# can-universalmodul.net
KiCad netlist of a schematic drawn in EAGLE
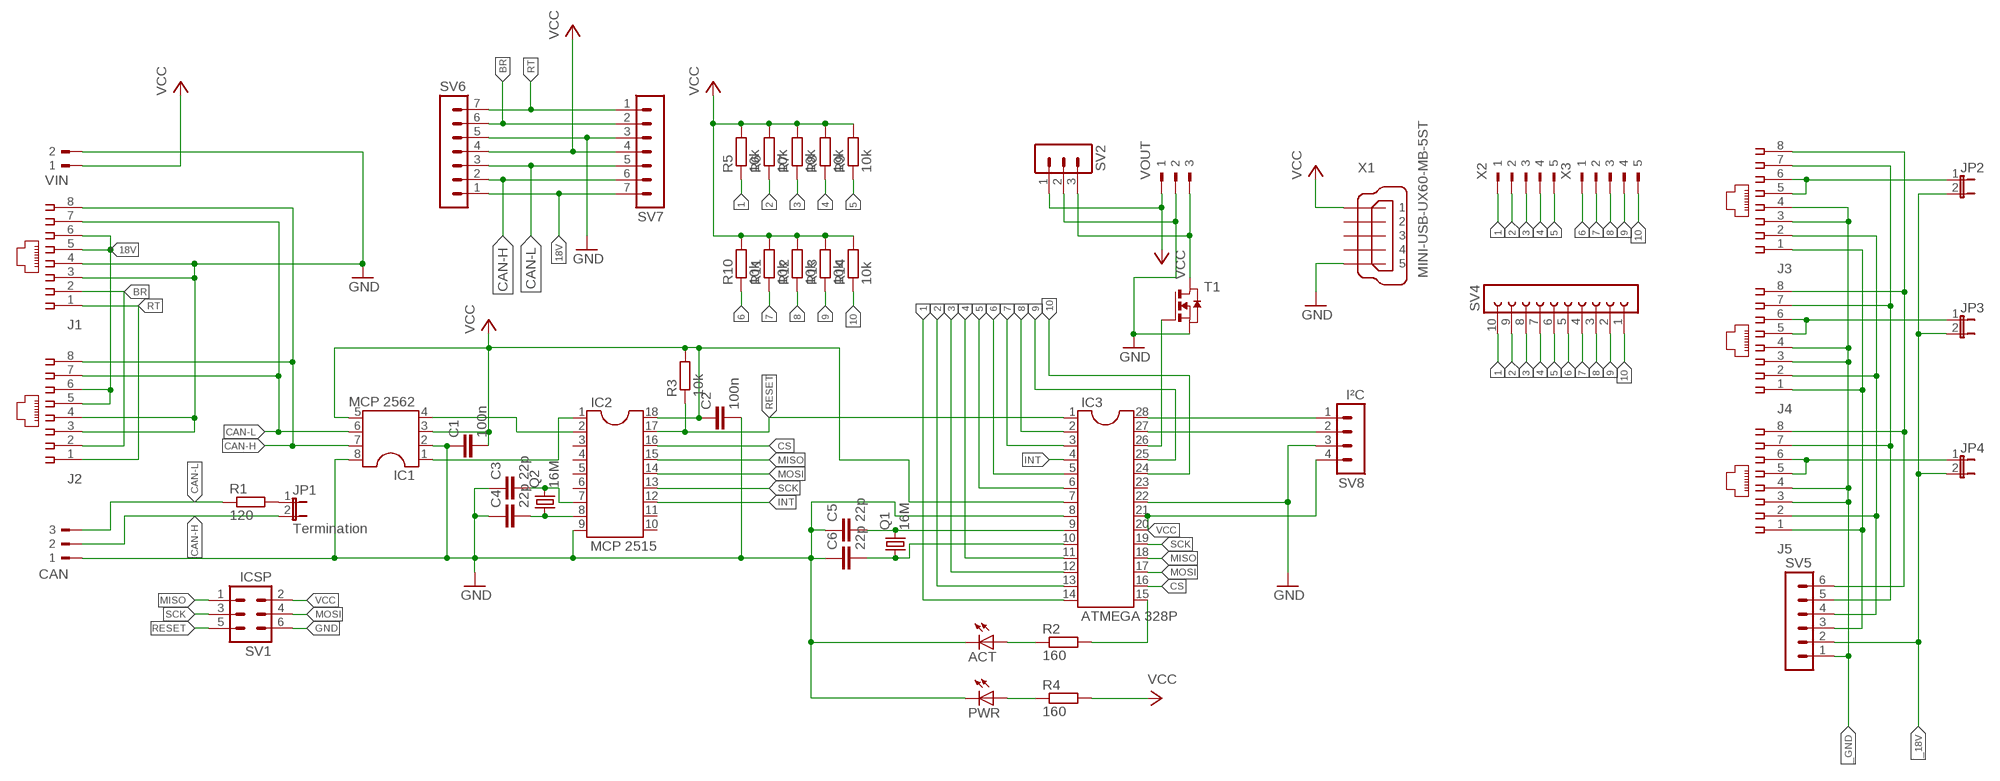
[diagram p0: schematic, sheet 1]

(export (version "E")
  (design (tool "Eeschema 10.0.6"))
  (components
    (comp (ref "ACT")
      (value "LEDCHIP-LED0805")
      (footprint "eagle-import:CHIP-LED0805")
      (libsource (lib "eagle-import") (part "LEDCHIP-LED0805"))
    )
    (comp (ref "C1")
      (value "100n")
      (footprint "eagle-import:C0805K")
      (libsource (lib "eagle-import") (part "C-EUC0805K"))
    )
    (comp (ref "C2")
      (value "100n")
      (footprint "eagle-import:C0805K")
      (libsource (lib "eagle-import") (part "C-EUC0805K"))
    )
    (comp (ref "C3")
      (value "22p")
      (footprint "eagle-import:C0805K")
      (libsource (lib "eagle-import") (part "C-EUC0805K"))
    )
    (comp (ref "C4")
      (value "22p")
      (footprint "eagle-import:C0805K")
      (libsource (lib "eagle-import") (part "C-EUC0805K"))
    )
    (comp (ref "C5")
      (value "22p")
      (footprint "eagle-import:C0805K")
      (libsource (lib "eagle-import") (part "C-EUC0805K"))
    )
    (comp (ref "C6")
      (value "22p")
      (footprint "eagle-import:C0805K")
      (libsource (lib "eagle-import") (part "C-EUC0805K"))
    )
    (comp (ref "CAN")
      (value "90-3")
      (footprint "eagle-import:90-3")
      (libsource (lib "eagle-import") (part "90-3"))
    )
    (comp (ref "IC1")
      (value "MCP 2562")
      (footprint "eagle-import:SOCKET-08")
      (libsource (lib "eagle-import") (part "DIL8S"))
    )
    (comp (ref "IC2")
      (value "MCP 2515")
      (footprint "eagle-import:SOCKET-18")
      (libsource (lib "eagle-import") (part "DIL18S"))
    )
    (comp (ref "IC3")
      (value "ATMEGA 328P")
      (footprint "eagle-import:DIL28-3")
      (libsource (lib "eagle-import") (part "DIL28-3"))
    )
    (comp (ref "J1")
      (value "215877-7")
      (footprint "eagle-import:215877-7")
      (libsource (lib "eagle-import") (part "215877-7"))
    )
    (comp (ref "J2")
      (value "215877-7")
      (footprint "eagle-import:215877-7")
      (libsource (lib "eagle-import") (part "215877-7"))
    )
    (comp (ref "J3")
      (value "215877-7")
      (footprint "eagle-import:215877-7")
      (libsource (lib "eagle-import") (part "215877-7"))
    )
    (comp (ref "J4")
      (value "215877-7")
      (footprint "eagle-import:215877-7")
      (libsource (lib "eagle-import") (part "215877-7"))
    )
    (comp (ref "J5")
      (value "215877-7")
      (footprint "eagle-import:215877-7")
      (libsource (lib "eagle-import") (part "215877-7"))
    )
    (comp (ref "JP1")
      (value "Termination")
      (footprint "eagle-import:JP1")
      (libsource (lib "eagle-import") (part "JP1E"))
    )
    (comp (ref "JP2")
      (value "JP1E")
      (footprint "eagle-import:JP1")
      (libsource (lib "eagle-import") (part "JP1E"))
    )
    (comp (ref "JP3")
      (value "JP1E")
      (footprint "eagle-import:JP1")
      (libsource (lib "eagle-import") (part "JP1E"))
    )
    (comp (ref "JP4")
      (value "JP1E")
      (footprint "eagle-import:JP1")
      (libsource (lib "eagle-import") (part "JP1E"))
    )
    (comp (ref "PWR")
      (value "LEDCHIP-LED0805")
      (footprint "eagle-import:CHIP-LED0805")
      (libsource (lib "eagle-import") (part "LEDCHIP-LED0805"))
    )
    (comp (ref "Q1")
      (value "16M")
      (footprint "eagle-import:CSM-7X-DU")
      (libsource (lib "eagle-import") (part "CSM-7X-DU"))
    )
    (comp (ref "Q2")
      (value "16M")
      (footprint "eagle-import:CSM-7X-DU")
      (libsource (lib "eagle-import") (part "CSM-7X-DU"))
    )
    (comp (ref "R1")
      (value "120")
      (footprint "eagle-import:R0805")
      (libsource (lib "eagle-import") (part "R-EU_R0805"))
    )
    (comp (ref "R2")
      (value "160")
      (footprint "eagle-import:R0805")
      (libsource (lib "eagle-import") (part "R-EU_R0805"))
    )
    (comp (ref "R3")
      (value "10k")
      (footprint "eagle-import:R0805")
      (libsource (lib "eagle-import") (part "R-EU_R0805"))
    )
    (comp (ref "R4")
      (value "160")
      (footprint "eagle-import:R0805")
      (libsource (lib "eagle-import") (part "R-EU_R0805"))
    )
    (comp (ref "R5")
      (value "10k")
      (footprint "eagle-import:R0805")
      (libsource (lib "eagle-import") (part "R-EU_R0805"))
    )
    (comp (ref "R6")
      (value "10k")
      (footprint "eagle-import:R0805")
      (libsource (lib "eagle-import") (part "R-EU_R0805"))
    )
    (comp (ref "R7")
      (value "10k")
      (footprint "eagle-import:R0805")
      (libsource (lib "eagle-import") (part "R-EU_R0805"))
    )
    (comp (ref "R8")
      (value "10k")
      (footprint "eagle-import:R0805")
      (libsource (lib "eagle-import") (part "R-EU_R0805"))
    )
    (comp (ref "R9")
      (value "10k")
      (footprint "eagle-import:R0805")
      (libsource (lib "eagle-import") (part "R-EU_R0805"))
    )
    (comp (ref "R10")
      (value "10k")
      (footprint "eagle-import:R0805")
      (libsource (lib "eagle-import") (part "R-EU_R0805"))
    )
    (comp (ref "R11")
      (value "10k")
      (footprint "eagle-import:R0805")
      (libsource (lib "eagle-import") (part "R-EU_R0805"))
    )
    (comp (ref "R12")
      (value "10k")
      (footprint "eagle-import:R0805")
      (libsource (lib "eagle-import") (part "R-EU_R0805"))
    )
    (comp (ref "R13")
      (value "10k")
      (footprint "eagle-import:R0805")
      (libsource (lib "eagle-import") (part "R-EU_R0805"))
    )
    (comp (ref "R14")
      (value "10k")
      (footprint "eagle-import:R0805")
      (libsource (lib "eagle-import") (part "R-EU_R0805"))
    )
    (comp (ref "SV1")
      (value "ICSP")
      (footprint "eagle-import:MA03-2")
      (libsource (lib "eagle-import") (part "MA03-2"))
    )
    (comp (ref "SV2")
      (value "MA03-1")
      (footprint "eagle-import:MA03-1")
      (libsource (lib "eagle-import") (part "MA03-1"))
    )
    (comp (ref "SV4")
      (value "FE10W")
      (footprint "eagle-import:FE10W")
      (libsource (lib "eagle-import") (part "FE10W"))
    )
    (comp (ref "SV5")
      (value "MA06-1")
      (footprint "eagle-import:MA06-1")
      (libsource (lib "eagle-import") (part "MA06-1"))
    )
    (comp (ref "SV6")
      (value "MA07-1")
      (footprint "eagle-import:MA07-1")
      (libsource (lib "eagle-import") (part "MA07-1"))
    )
    (comp (ref "SV7")
      (value "MA07-1")
      (footprint "eagle-import:MA07-1")
      (libsource (lib "eagle-import") (part "MA07-1"))
    )
    (comp (ref "SV8")
      (value "I²C")
      (footprint "eagle-import:MA04-1")
      (libsource (lib "eagle-import") (part "MA04-1"))
    )
    (comp (ref "T1")
      (value "NMOSSOT23")
      (footprint "eagle-import:SOT-23")
      (libsource (lib "eagle-import") (part "NMOSSOT23"))
    )
    (comp (ref "VIN")
      (value "90-2")
      (footprint "eagle-import:90-2")
      (libsource (lib "eagle-import") (part "90-2"))
    )
    (comp (ref "VOUT")
      (value "90-3")
      (footprint "eagle-import:90-3")
      (libsource (lib "eagle-import") (part "90-3"))
    )
    (comp (ref "X1")
      (value "MINI-USB-UX60-MB-5ST")
      (footprint "eagle-import:UX60-MB-5ST")
      (libsource (lib "eagle-import") (part "MINI-USB-UX60-MB-5ST"))
    )
    (comp (ref "X2")
      (value "90-5")
      (footprint "eagle-import:90-5")
      (libsource (lib "eagle-import") (part "90-5"))
    )
    (comp (ref "X3")
      (value "90-5")
      (footprint "eagle-import:90-5")
      (libsource (lib "eagle-import") (part "90-5"))
    )
  )
  (nets
    (net (code "1") (name "1") (class "Default")
      (node (ref "IC3") (pin "14") (pinfunction "14_14") (pintype "passive"))
      (node (ref "R5") (pin "1") (pinfunction "1_1") (pintype "passive"))
      (node (ref "SV4") (pin "10") (pinfunction "10_10") (pintype "passive"))
      (node (ref "X2") (pin "1") (pinfunction "1_1") (pintype "passive"))
    )
    (net (code "2") (name "2") (class "Default")
      (node (ref "IC3") (pin "13") (pinfunction "13_13") (pintype "passive"))
      (node (ref "R6") (pin "1") (pinfunction "1_1") (pintype "passive"))
      (node (ref "SV4") (pin "9") (pinfunction "9_9") (pintype "passive"))
      (node (ref "X2") (pin "2") (pinfunction "2_2") (pintype "passive"))
    )
    (net (code "3") (name "3") (class "Default")
      (node (ref "IC3") (pin "12") (pinfunction "12_12") (pintype "passive"))
      (node (ref "R7") (pin "1") (pinfunction "1_1") (pintype "passive"))
      (node (ref "SV4") (pin "8") (pinfunction "8_8") (pintype "passive"))
      (node (ref "X2") (pin "3") (pinfunction "3_3") (pintype "passive"))
    )
    (net (code "4") (name "4") (class "Default")
      (node (ref "IC3") (pin "11") (pinfunction "11_11") (pintype "passive"))
      (node (ref "R8") (pin "1") (pinfunction "1_1") (pintype "passive"))
      (node (ref "SV4") (pin "7") (pinfunction "7_7") (pintype "passive"))
      (node (ref "X2") (pin "4") (pinfunction "4_4") (pintype "passive"))
    )
    (net (code "5") (name "5") (class "Default")
      (node (ref "IC3") (pin "6") (pinfunction "6_6") (pintype "passive"))
      (node (ref "R9") (pin "1") (pinfunction "1_1") (pintype "passive"))
      (node (ref "SV4") (pin "6") (pinfunction "6_6") (pintype "passive"))
      (node (ref "X2") (pin "5") (pinfunction "5_5") (pintype "passive"))
    )
    (net (code "6") (name "6") (class "Default")
      (node (ref "IC3") (pin "5") (pinfunction "5_5") (pintype "passive"))
      (node (ref "R10") (pin "1") (pinfunction "1_1") (pintype "passive"))
      (node (ref "SV4") (pin "5") (pinfunction "5_5") (pintype "passive"))
      (node (ref "X3") (pin "1") (pinfunction "1_1") (pintype "passive"))
    )
    (net (code "7") (name "7") (class "Default")
      (node (ref "IC3") (pin "3") (pinfunction "3_3") (pintype "passive"))
      (node (ref "R11") (pin "1") (pinfunction "1_1") (pintype "passive"))
      (node (ref "SV4") (pin "4") (pinfunction "4_4") (pintype "passive"))
      (node (ref "X3") (pin "2") (pinfunction "2_2") (pintype "passive"))
    )
    (net (code "8") (name "8") (class "Default")
      (node (ref "IC3") (pin "2") (pinfunction "2_2") (pintype "passive"))
      (node (ref "R12") (pin "1") (pinfunction "1_1") (pintype "passive"))
      (node (ref "SV4") (pin "3") (pinfunction "3_3") (pintype "passive"))
      (node (ref "X3") (pin "3") (pinfunction "3_3") (pintype "passive"))
    )
    (net (code "9") (name "9") (class "Default")
      (node (ref "IC3") (pin "25") (pinfunction "25_25") (pintype "passive"))
      (node (ref "R13") (pin "1") (pinfunction "1_1") (pintype "passive"))
      (node (ref "SV4") (pin "2") (pinfunction "2_2") (pintype "passive"))
      (node (ref "X3") (pin "4") (pinfunction "4_4") (pintype "passive"))
    )
    (net (code "10") (name "10") (class "Default")
      (node (ref "IC3") (pin "24") (pinfunction "24_24") (pintype "passive"))
      (node (ref "R14") (pin "1") (pinfunction "1_1") (pintype "passive"))
      (node (ref "SV4") (pin "1") (pinfunction "1_1") (pintype "passive"))
      (node (ref "X3") (pin "5") (pinfunction "5_5") (pintype "passive"))
    )
    (net (code "11") (name "18V") (class "Default")
      (node (ref "J1") (pin "5") (pinfunction "5_5") (pintype "passive"))
      (node (ref "J1") (pin "6") (pinfunction "6_6") (pintype "passive"))
      (node (ref "J2") (pin "5") (pinfunction "5_5") (pintype "passive"))
      (node (ref "J2") (pin "6") (pinfunction "6_6") (pintype "passive"))
      (node (ref "SV6") (pin "1") (pinfunction "1_1") (pintype "passive"))
      (node (ref "SV7") (pin "7") (pinfunction "7_7") (pintype "passive"))
    )
    (net (code "12") (name "BR") (class "Default")
      (node (ref "J1") (pin "2") (pinfunction "2_2") (pintype "passive"))
      (node (ref "J2") (pin "2") (pinfunction "2_2") (pintype "passive"))
      (node (ref "SV6") (pin "6") (pinfunction "6_6") (pintype "passive"))
      (node (ref "SV7") (pin "2") (pinfunction "2_2") (pintype "passive"))
    )
    (net (code "13") (name "CAN-H") (class "Default")
      (node (ref "CAN") (pin "2") (pinfunction "2_2") (pintype "passive"))
      (node (ref "IC1") (pin "7") (pinfunction "7_7") (pintype "passive"))
      (node (ref "J1") (pin "8") (pinfunction "8_8") (pintype "passive"))
      (node (ref "J2") (pin "8") (pinfunction "8_8") (pintype "passive"))
      (node (ref "JP1") (pin "2") (pinfunction "2_2") (pintype "passive"))
      (node (ref "SV6") (pin "2") (pinfunction "2_2") (pintype "passive"))
      (node (ref "SV7") (pin "6") (pinfunction "6_6") (pintype "passive"))
    )
    (net (code "14") (name "CAN-L") (class "Default")
      (node (ref "CAN") (pin "3") (pinfunction "3_3") (pintype "passive"))
      (node (ref "IC1") (pin "6") (pinfunction "6_6") (pintype "passive"))
      (node (ref "J1") (pin "7") (pinfunction "7_7") (pintype "passive"))
      (node (ref "J2") (pin "7") (pinfunction "7_7") (pintype "passive"))
      (node (ref "R1") (pin "1") (pinfunction "1_1") (pintype "passive"))
      (node (ref "SV6") (pin "3") (pinfunction "3_3") (pintype "passive"))
      (node (ref "SV7") (pin "5") (pinfunction "5_5") (pintype "passive"))
    )
    (net (code "15") (name "CS") (class "Default")
      (node (ref "IC2") (pin "16") (pinfunction "16_16") (pintype "passive"))
      (node (ref "IC3") (pin "16") (pinfunction "16_16") (pintype "passive"))
    )
    (net (code "16") (name "GND") (class "Default")
      (node (ref "ACT") (pin "C") (pinfunction "C_C") (pintype "passive"))
      (node (ref "C1") (pin "1") (pinfunction "1_1") (pintype "passive"))
      (node (ref "C2") (pin "2") (pinfunction "2_2") (pintype "passive"))
      (node (ref "C3") (pin "1") (pinfunction "1_1") (pintype "passive"))
      (node (ref "C4") (pin "1") (pinfunction "1_1") (pintype "passive"))
      (node (ref "C5") (pin "1") (pinfunction "1_1") (pintype "passive"))
      (node (ref "C6") (pin "1") (pinfunction "1_1") (pintype "passive"))
      (node (ref "CAN") (pin "1") (pinfunction "1_1") (pintype "passive"))
      (node (ref "IC1") (pin "2") (pinfunction "2_2") (pintype "passive"))
      (node (ref "IC1") (pin "8") (pinfunction "8_8") (pintype "passive"))
      (node (ref "IC2") (pin "9") (pinfunction "9_9") (pintype "passive"))
      (node (ref "IC3") (pin "22") (pinfunction "22_22") (pintype "passive"))
      (node (ref "IC3") (pin "8") (pinfunction "8_8") (pintype "passive"))
      (node (ref "J1") (pin "3") (pinfunction "3_3") (pintype "passive"))
      (node (ref "J1") (pin "4") (pinfunction "4_4") (pintype "passive"))
      (node (ref "J2") (pin "3") (pinfunction "3_3") (pintype "passive"))
      (node (ref "J2") (pin "4") (pinfunction "4_4") (pintype "passive"))
      (node (ref "PWR") (pin "C") (pinfunction "C_C") (pintype "passive"))
      (node (ref "SV1") (pin "6") (pinfunction "6_6") (pintype "passive"))
      (node (ref "SV2") (pin "2") (pinfunction "2_2") (pintype "passive"))
      (node (ref "SV6") (pin "5") (pinfunction "5_5") (pintype "passive"))
      (node (ref "SV7") (pin "3") (pinfunction "3_3") (pintype "passive"))
      (node (ref "SV8") (pin "3") (pinfunction "3_3") (pintype "passive"))
      (node (ref "T1") (pin "2") (pinfunction "S_2") (pintype "passive"))
      (node (ref "VIN") (pin "2") (pinfunction "2_2") (pintype "passive"))
      (node (ref "VOUT") (pin "2") (pinfunction "2_2") (pintype "passive"))
      (node (ref "X1") (pin "5") (pinfunction "5_5") (pintype "input"))
    )
    (net (code "17") (name "INT") (class "Default")
      (node (ref "IC2") (pin "12") (pinfunction "12_12") (pintype "passive"))
      (node (ref "IC3") (pin "4") (pinfunction "4_4") (pintype "passive"))
    )
    (net (code "18") (name "MISO") (class "Default")
      (node (ref "IC2") (pin "15") (pinfunction "15_15") (pintype "passive"))
      (node (ref "IC3") (pin "18") (pinfunction "18_18") (pintype "passive"))
      (node (ref "SV1") (pin "1") (pinfunction "1_1") (pintype "passive"))
    )
    (net (code "19") (name "MOSI") (class "Default")
      (node (ref "IC2") (pin "14") (pinfunction "14_14") (pintype "passive"))
      (node (ref "IC3") (pin "17") (pinfunction "17_17") (pintype "passive"))
      (node (ref "SV1") (pin "4") (pinfunction "4_4") (pintype "passive"))
    )
    (net (code "20") (name "Net-(ACT-PadA)") (class "Default")
      (node (ref "ACT") (pin "A") (pinfunction "A_A") (pintype "passive"))
      (node (ref "R2") (pin "1") (pinfunction "1_1") (pintype "passive"))
    )
    (net (code "21") (name "Net-(C3-Pad2)") (class "Default")
      (node (ref "C3") (pin "2") (pinfunction "2_2") (pintype "passive"))
      (node (ref "IC2") (pin "7") (pinfunction "7_7") (pintype "passive"))
      (node (ref "Q2") (pin "2") (pinfunction "2_2") (pintype "passive"))
    )
    (net (code "22") (name "Net-(C4-Pad2)") (class "Default")
      (node (ref "C4") (pin "2") (pinfunction "2_2") (pintype "passive"))
      (node (ref "IC2") (pin "8") (pinfunction "8_8") (pintype "passive"))
      (node (ref "Q2") (pin "1") (pinfunction "1_1") (pintype "passive"))
    )
    (net (code "23") (name "Net-(C5-Pad2)") (class "Default")
      (node (ref "C5") (pin "2") (pinfunction "2_2") (pintype "passive"))
      (node (ref "IC3") (pin "9") (pinfunction "9_9") (pintype "passive"))
      (node (ref "Q1") (pin "2") (pinfunction "2_2") (pintype "passive"))
    )
    (net (code "24") (name "Net-(C6-Pad2)") (class "Default")
      (node (ref "C6") (pin "2") (pinfunction "2_2") (pintype "passive"))
      (node (ref "IC3") (pin "10") (pinfunction "10_10") (pintype "passive"))
      (node (ref "Q1") (pin "1") (pinfunction "1_1") (pintype "passive"))
    )
    (net (code "25") (name "Net-(IC1-Pad1)") (class "Default")
      (node (ref "IC1") (pin "1") (pinfunction "1_1") (pintype "passive"))
      (node (ref "IC2") (pin "1") (pinfunction "1_1") (pintype "passive"))
    )
    (net (code "26") (name "Net-(IC1-Pad4)") (class "Default")
      (node (ref "IC1") (pin "4") (pinfunction "4_4") (pintype "passive"))
      (node (ref "IC2") (pin "2") (pinfunction "2_2") (pintype "passive"))
    )
    (net (code "27") (name "Net-(IC3-Pad15)") (class "Default")
      (node (ref "IC3") (pin "15") (pinfunction "15_15") (pintype "passive"))
      (node (ref "R2") (pin "2") (pinfunction "2_2") (pintype "passive"))
    )
    (net (code "28") (name "Net-(IC3-Pad27)") (class "Default")
      (node (ref "IC3") (pin "27") (pinfunction "27_27") (pintype "passive"))
      (node (ref "SV8") (pin "2") (pinfunction "2_2") (pintype "passive"))
    )
    (net (code "29") (name "Net-(IC3-Pad28)") (class "Default")
      (node (ref "IC3") (pin "28") (pinfunction "28_28") (pintype "passive"))
      (node (ref "SV8") (pin "1") (pinfunction "1_1") (pintype "passive"))
    )
    (net (code "30") (name "Net-(J3-Pad1)") (class "Default")
      (node (ref "J3") (pin "1") (pinfunction "1_1") (pintype "passive"))
      (node (ref "J4") (pin "1") (pinfunction "1_1") (pintype "passive"))
      (node (ref "J5") (pin "1") (pinfunction "1_1") (pintype "passive"))
      (node (ref "SV5") (pin "3") (pinfunction "3_3") (pintype "passive"))
    )
    (net (code "31") (name "Net-(J3-Pad2)") (class "Default")
      (node (ref "J3") (pin "2") (pinfunction "2_2") (pintype "passive"))
      (node (ref "J4") (pin "2") (pinfunction "2_2") (pintype "passive"))
      (node (ref "J5") (pin "2") (pinfunction "2_2") (pintype "passive"))
      (node (ref "SV5") (pin "4") (pinfunction "4_4") (pintype "passive"))
    )
    (net (code "32") (name "Net-(J3-Pad5)") (class "Default")
      (node (ref "J3") (pin "5") (pinfunction "5_5") (pintype "passive"))
      (node (ref "J3") (pin "6") (pinfunction "6_6") (pintype "passive"))
      (node (ref "JP2") (pin "1") (pinfunction "1_1") (pintype "passive"))
    )
    (net (code "33") (name "Net-(J3-Pad7)") (class "Default")
      (node (ref "J3") (pin "7") (pinfunction "7_7") (pintype "passive"))
      (node (ref "J4") (pin "7") (pinfunction "7_7") (pintype "passive"))
      (node (ref "J5") (pin "7") (pinfunction "7_7") (pintype "passive"))
      (node (ref "SV5") (pin "5") (pinfunction "5_5") (pintype "passive"))
    )
    (net (code "34") (name "Net-(J3-Pad8)") (class "Default")
      (node (ref "J3") (pin "8") (pinfunction "8_8") (pintype "passive"))
      (node (ref "J4") (pin "8") (pinfunction "8_8") (pintype "passive"))
      (node (ref "J5") (pin "8") (pinfunction "8_8") (pintype "passive"))
      (node (ref "SV5") (pin "6") (pinfunction "6_6") (pintype "passive"))
    )
    (net (code "35") (name "Net-(J4-Pad5)") (class "Default")
      (node (ref "J4") (pin "5") (pinfunction "5_5") (pintype "passive"))
      (node (ref "J4") (pin "6") (pinfunction "6_6") (pintype "passive"))
      (node (ref "JP3") (pin "1") (pinfunction "1_1") (pintype "passive"))
    )
    (net (code "36") (name "Net-(J5-Pad5)") (class "Default")
      (node (ref "J5") (pin "5") (pinfunction "5_5") (pintype "passive"))
      (node (ref "J5") (pin "6") (pinfunction "6_6") (pintype "passive"))
      (node (ref "JP4") (pin "1") (pinfunction "1_1") (pintype "passive"))
    )
    (net (code "37") (name "Net-(JP1-Pad1)") (class "Default")
      (node (ref "JP1") (pin "1") (pinfunction "1_1") (pintype "passive"))
      (node (ref "R1") (pin "2") (pinfunction "2_2") (pintype "passive"))
    )
    (net (code "38") (name "Net-(PWR-PadA)") (class "Default")
      (node (ref "PWR") (pin "A") (pinfunction "A_A") (pintype "passive"))
      (node (ref "R4") (pin "1") (pinfunction "1_1") (pintype "passive"))
    )
    (net (code "39") (name "Net-(T1-D)") (class "Default")
      (node (ref "SV2") (pin "3") (pinfunction "3_3") (pintype "passive"))
      (node (ref "T1") (pin "1") (pinfunction "D_1") (pintype "passive"))
      (node (ref "VOUT") (pin "3") (pinfunction "3_3") (pintype "passive"))
    )
    (net (code "40") (name "Net-(T1-G)") (class "Default")
      (node (ref "IC3") (pin "26") (pinfunction "26_26") (pintype "passive"))
      (node (ref "T1") (pin "3") (pinfunction "G_3") (pintype "passive"))
    )
    (net (code "41") (name "RESET") (class "Default")
      (node (ref "IC2") (pin "17") (pinfunction "17_17") (pintype "passive"))
      (node (ref "IC3") (pin "1") (pinfunction "1_1") (pintype "passive"))
      (node (ref "R3") (pin "1") (pinfunction "1_1") (pintype "passive"))
      (node (ref "SV1") (pin "5") (pinfunction "5_5") (pintype "passive"))
    )
    (net (code "42") (name "RT") (class "Default")
      (node (ref "J1") (pin "1") (pinfunction "1_1") (pintype "passive"))
      (node (ref "J2") (pin "1") (pinfunction "1_1") (pintype "passive"))
      (node (ref "SV6") (pin "7") (pinfunction "7_7") (pintype "passive"))
      (node (ref "SV7") (pin "1") (pinfunction "1_1") (pintype "passive"))
    )
    (net (code "43") (name "SCK") (class "Default")
      (node (ref "IC2") (pin "13") (pinfunction "13_13") (pintype "passive"))
      (node (ref "IC3") (pin "19") (pinfunction "19_19") (pintype "passive"))
      (node (ref "SV1") (pin "3") (pinfunction "3_3") (pintype "passive"))
    )
    (net (code "44") (name "VCC") (class "Default")
      (node (ref "C1") (pin "2") (pinfunction "2_2") (pintype "passive"))
      (node (ref "C2") (pin "1") (pinfunction "1_1") (pintype "passive"))
      (node (ref "IC1") (pin "3") (pinfunction "3_3") (pintype "passive"))
      (node (ref "IC1") (pin "5") (pinfunction "5_5") (pintype "passive"))
      (node (ref "IC2") (pin "18") (pinfunction "18_18") (pintype "passive"))
      (node (ref "IC3") (pin "20") (pinfunction "20_20") (pintype "passive"))
      (node (ref "IC3") (pin "21") (pinfunction "21_21") (pintype "passive"))
      (node (ref "IC3") (pin "7") (pinfunction "7_7") (pintype "passive"))
      (node (ref "R10") (pin "2") (pinfunction "2_2") (pintype "passive"))
      (node (ref "R11") (pin "2") (pinfunction "2_2") (pintype "passive"))
      (node (ref "R12") (pin "2") (pinfunction "2_2") (pintype "passive"))
      (node (ref "R13") (pin "2") (pinfunction "2_2") (pintype "passive"))
      (node (ref "R14") (pin "2") (pinfunction "2_2") (pintype "passive"))
      (node (ref "R3") (pin "2") (pinfunction "2_2") (pintype "passive"))
      (node (ref "R4") (pin "2") (pinfunction "2_2") (pintype "passive"))
      (node (ref "R5") (pin "2") (pinfunction "2_2") (pintype "passive"))
      (node (ref "R6") (pin "2") (pinfunction "2_2") (pintype "passive"))
      (node (ref "R7") (pin "2") (pinfunction "2_2") (pintype "passive"))
      (node (ref "R8") (pin "2") (pinfunction "2_2") (pintype "passive"))
      (node (ref "R9") (pin "2") (pinfunction "2_2") (pintype "passive"))
      (node (ref "SV1") (pin "2") (pinfunction "2_2") (pintype "passive"))
      (node (ref "SV2") (pin "1") (pinfunction "1_1") (pintype "passive"))
      (node (ref "SV6") (pin "4") (pinfunction "4_4") (pintype "passive"))
      (node (ref "SV7") (pin "4") (pinfunction "4_4") (pintype "passive"))
      (node (ref "SV8") (pin "4") (pinfunction "4_4") (pintype "passive"))
      (node (ref "VIN") (pin "1") (pinfunction "1_1") (pintype "passive"))
      (node (ref "VOUT") (pin "1") (pinfunction "1_1") (pintype "passive"))
      (node (ref "X1") (pin "1") (pinfunction "1_1") (pintype "input"))
    )
    (net (code "45") (name "_18V") (class "Default")
      (node (ref "JP2") (pin "2") (pinfunction "2_2") (pintype "passive"))
      (node (ref "JP3") (pin "2") (pinfunction "2_2") (pintype "passive"))
      (node (ref "JP4") (pin "2") (pinfunction "2_2") (pintype "passive"))
      (node (ref "SV5") (pin "2") (pinfunction "2_2") (pintype "passive"))
    )
    (net (code "46") (name "_GND") (class "Default")
      (node (ref "J3") (pin "3") (pinfunction "3_3") (pintype "passive"))
      (node (ref "J3") (pin "4") (pinfunction "4_4") (pintype "passive"))
      (node (ref "J4") (pin "3") (pinfunction "3_3") (pintype "passive"))
      (node (ref "J4") (pin "4") (pinfunction "4_4") (pintype "passive"))
      (node (ref "J5") (pin "3") (pinfunction "3_3") (pintype "passive"))
      (node (ref "J5") (pin "4") (pinfunction "4_4") (pintype "passive"))
      (node (ref "SV5") (pin "1") (pinfunction "1_1") (pintype "passive"))
    )
    (net (code "47") (name "unconnected-(IC2-Pad3)") (class "Default")
      (node (ref "IC2") (pin "3") (pinfunction "3_3") (pintype "passive"))
    )
    (net (code "48") (name "unconnected-(IC2-Pad4)") (class "Default")
      (node (ref "IC2") (pin "4") (pinfunction "4_4") (pintype "passive"))
    )
    (net (code "49") (name "unconnected-(IC2-Pad5)") (class "Default")
      (node (ref "IC2") (pin "5") (pinfunction "5_5") (pintype "passive"))
    )
    (net (code "50") (name "unconnected-(IC2-Pad6)") (class "Default")
      (node (ref "IC2") (pin "6") (pinfunction "6_6") (pintype "passive"))
    )
    (net (code "51") (name "unconnected-(IC2-Pad10)") (class "Default")
      (node (ref "IC2") (pin "10") (pinfunction "10_10") (pintype "passive"))
    )
    (net (code "52") (name "unconnected-(IC2-Pad11)") (class "Default")
      (node (ref "IC2") (pin "11") (pinfunction "11_11") (pintype "passive"))
    )
    (net (code "53") (name "unconnected-(IC3-Pad23)") (class "Default")
      (node (ref "IC3") (pin "23") (pinfunction "23_23") (pintype "passive"))
    )
    (net (code "54") (name "unconnected-(X1-Pad2)") (class "Default")
      (node (ref "X1") (pin "2") (pinfunction "2_2") (pintype "input"))
    )
    (net (code "55") (name "unconnected-(X1-Pad3)") (class "Default")
      (node (ref "X1") (pin "3") (pinfunction "3_3") (pintype "input"))
    )
    (net (code "56") (name "unconnected-(X1-Pad4)") (class "Default")
      (node (ref "X1") (pin "4") (pinfunction "4_4") (pintype "input"))
    )
  )
)
